# ESP32_Clock_Easy.net
KiCad netlist of a schematic drawn in EasyEDA
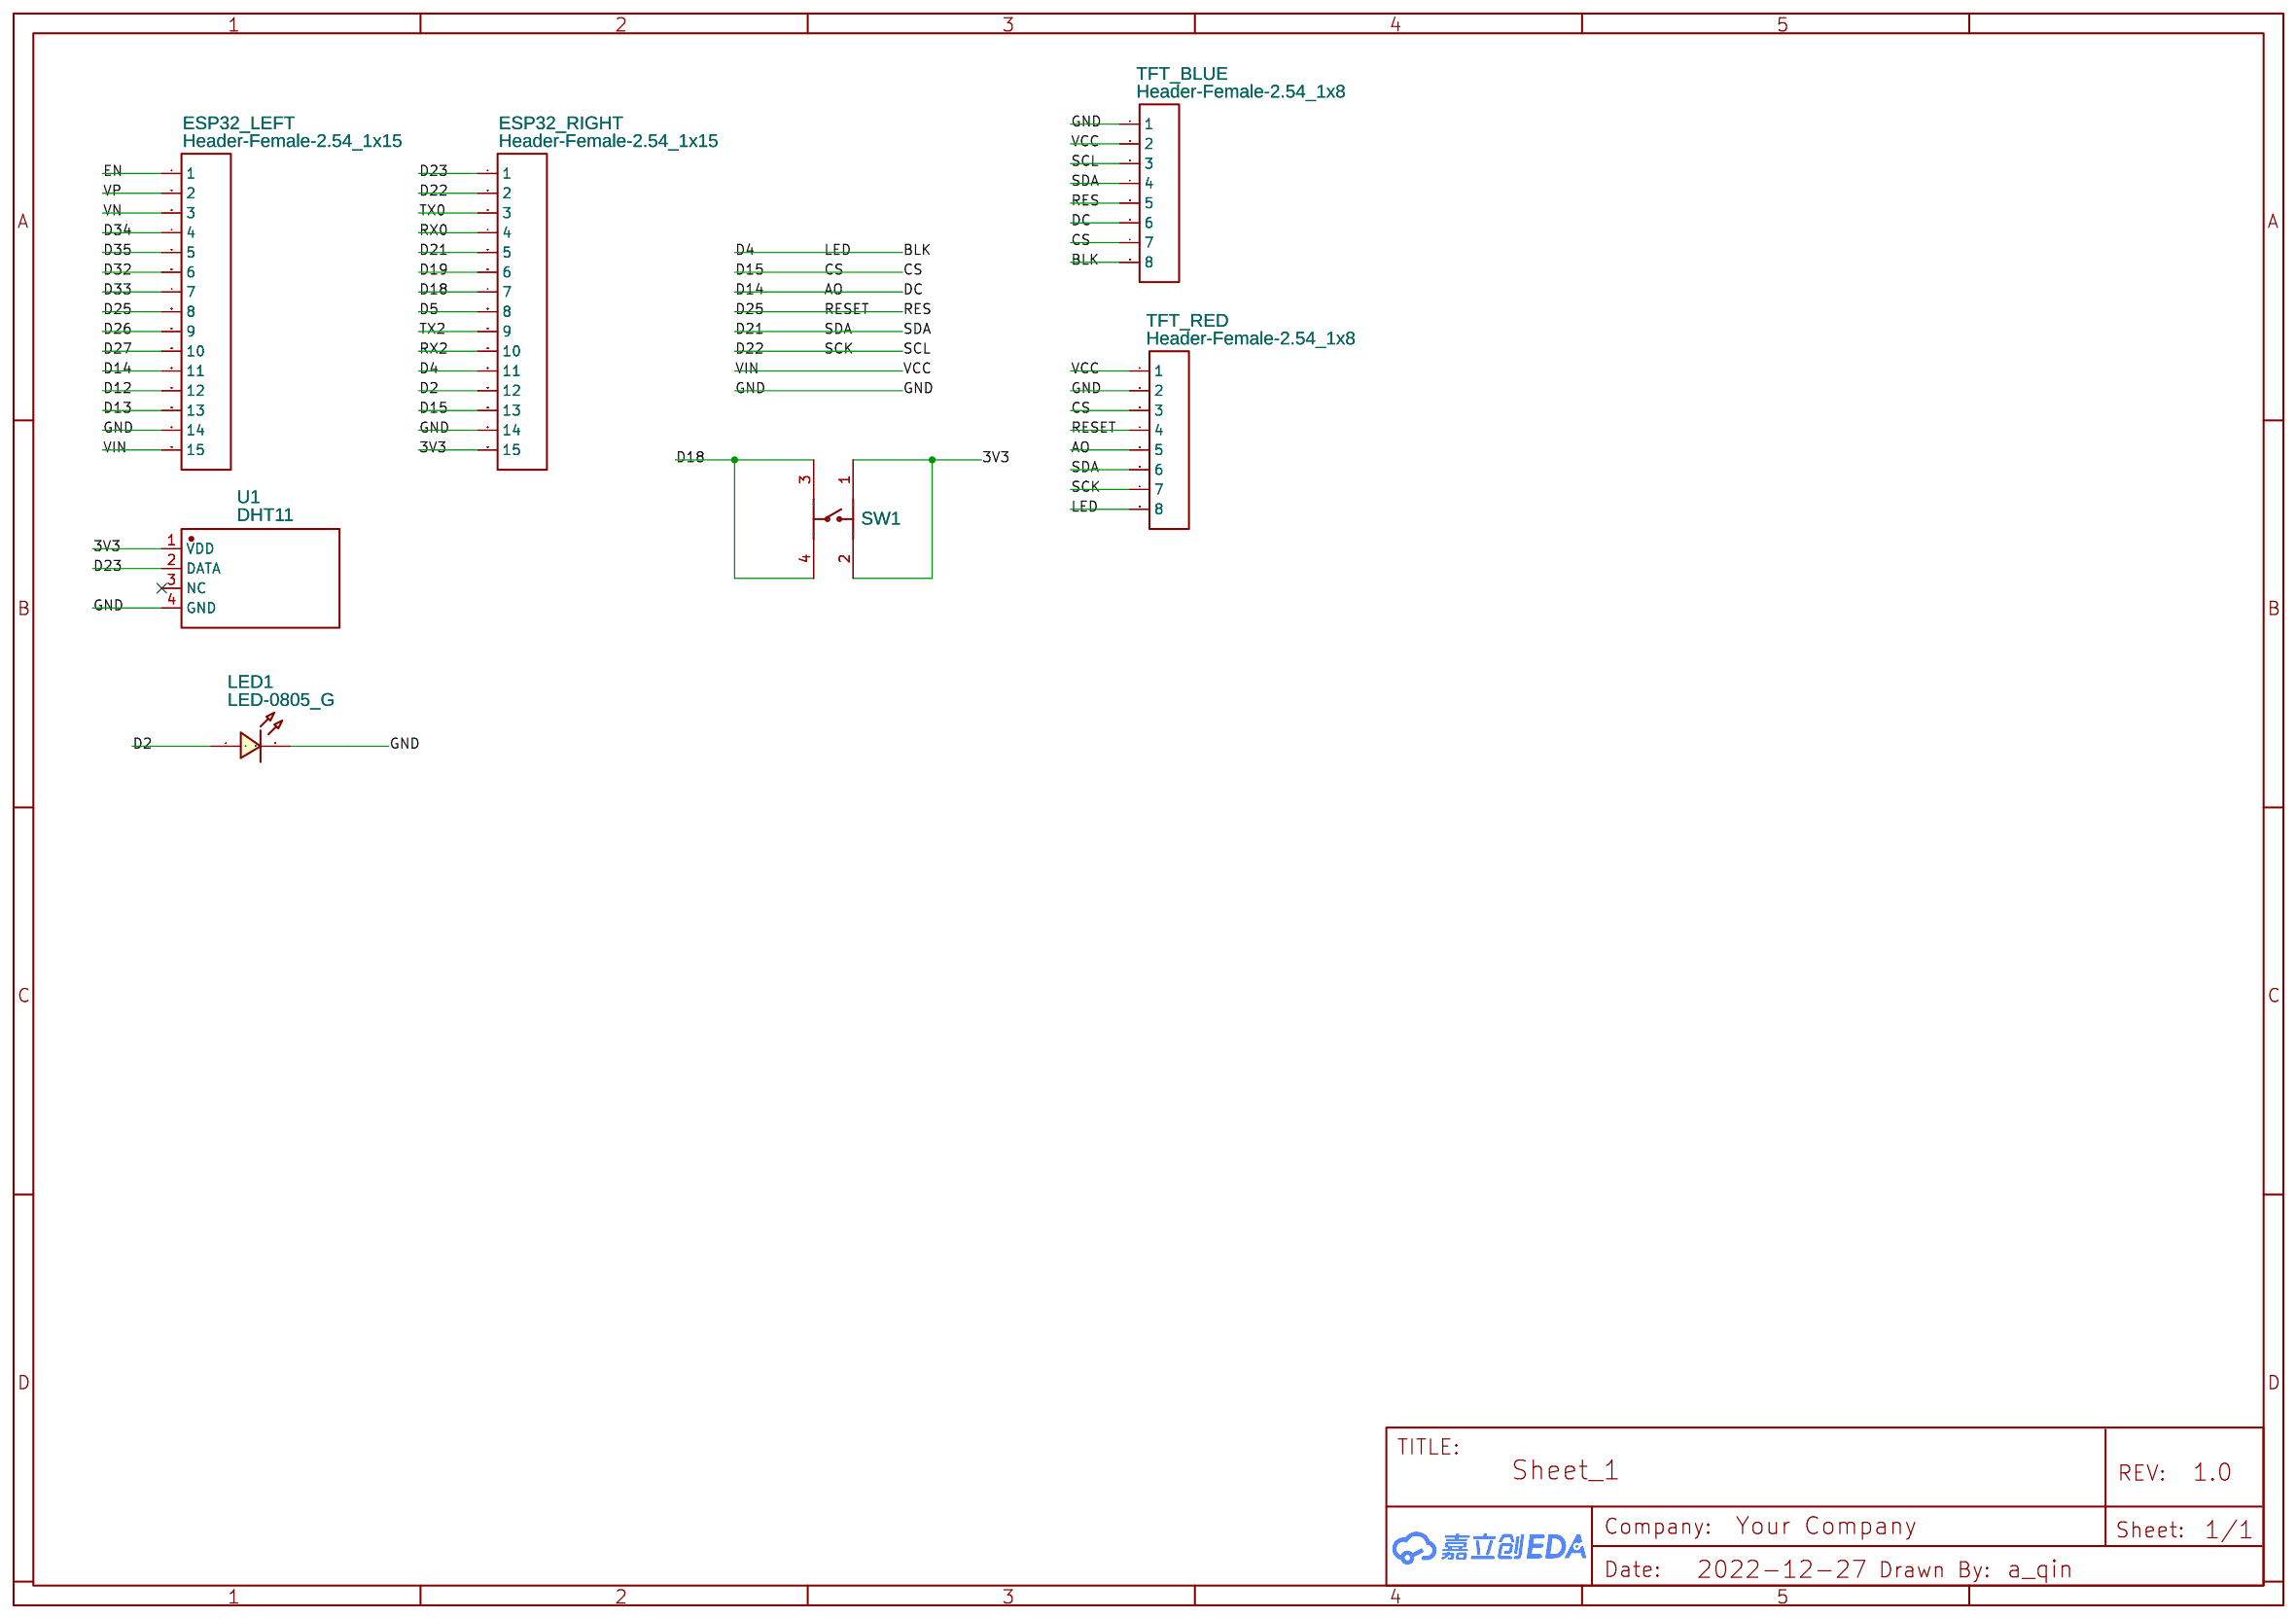
[diagram p0: schematic sheet]

(export (version "E")
  (design (tool "Eeschema 10.0.6"))
  (components
    (comp (ref "ESP32_LEFT")
      (value "Header-Female-2.54_1x15")
      (fields
        (field (name "BOM_Manufacturer Part") "B-2200S15P-A120")
        (field (name "BOM_Supplier Part") "C124408")
      )
      (libsource (lib "") (part "Header-Female-2.54_1x15"))
    )
    (comp (ref "ESP32_RIGHT")
      (value "Header-Female-2.54_1x15")
      (fields
        (field (name "BOM_Manufacturer Part") "B-2200S15P-A120")
        (field (name "BOM_Supplier Part") "C124408")
      )
      (libsource (lib "") (part "Header-Female-2.54_1x15_1"))
    )
    (comp (ref "LED1")
      (value "LED-0805_G")
      (fields (field (name "BOM_Manufacturer Part") "NCD0805G1") (field (name "BOM_Supplier Part") "C84260"))
      (libsource (lib "") (part "LED-0805_G"))
    )
    (comp (ref "SW1")
      (value "PTS645SK50-2LFS")
      (fields (field (name "BOM_Supplier Part") "C2689653"))
      (libsource (lib "") (part "PTS645SK50-2LFS"))
    )
    (comp (ref "TFT_BLUE")
      (value "Header-Female-2.54_1x8")
      (fields
        (field (name "BOM_Manufacturer Part") "2.54-1*8P母环保")
        (field (name "BOM_Supplier Part") "C27438")
      )
      (libsource (lib "") (part "Header-Female-2.54_1x8"))
    )
    (comp (ref "TFT_RED")
      (value "Header-Female-2.54_1x8")
      (fields
        (field (name "BOM_Manufacturer Part") "2.54-1*8P母环保")
        (field (name "BOM_Supplier Part") "C27438")
      )
      (libsource (lib "") (part "Header-Female-2.54_1x8_1"))
    )
    (comp (ref "U1")
      (value "DHT11")
      (fields (field (name "BOM_Supplier Part") "C117051"))
      (libsource (lib "") (part "DHT11"))
    )
  )
  (nets
    (net (code "1") (name "/3V3") (class "Default")
      (node (ref "ESP32_RIGHT") (pin "15") (pinfunction "15_15") (pintype "unspecified"))
      (node (ref "SW1") (pin "1") (pinfunction "1_1") (pintype "unspecified"))
      (node (ref "SW1") (pin "2") (pinfunction "2_2") (pintype "unspecified"))
      (node (ref "U1") (pin "1") (pinfunction "VDD_1") (pintype "unspecified"))
    )
    (net (code "2") (name "/AO") (class "Default")
      (node (ref "ESP32_LEFT") (pin "11") (pinfunction "11_11") (pintype "unspecified"))
      (node (ref "TFT_BLUE") (pin "6") (pinfunction "6_6") (pintype "input"))
      (node (ref "TFT_RED") (pin "5") (pinfunction "5_5") (pintype "input"))
    )
    (net (code "3") (name "/BLK") (class "Default")
      (node (ref "ESP32_RIGHT") (pin "11") (pinfunction "11_11") (pintype "unspecified"))
      (node (ref "TFT_BLUE") (pin "8") (pinfunction "8_8") (pintype "input"))
      (node (ref "TFT_RED") (pin "8") (pinfunction "8_8") (pintype "input"))
    )
    (net (code "4") (name "/CS") (class "Default")
      (node (ref "ESP32_RIGHT") (pin "13") (pinfunction "13_13") (pintype "unspecified"))
      (node (ref "TFT_BLUE") (pin "7") (pinfunction "7_7") (pintype "input"))
      (node (ref "TFT_RED") (pin "3") (pinfunction "3_3") (pintype "input"))
    )
    (net (code "5") (name "/D2") (class "Default")
      (node (ref "ESP32_RIGHT") (pin "12") (pinfunction "12_12") (pintype "unspecified"))
      (node (ref "LED1") (pin "1") (pinfunction "1_1") (pintype "unspecified"))
    )
    (net (code "6") (name "/D5") (class "Default")
      (node (ref "ESP32_RIGHT") (pin "8") (pinfunction "8_8") (pintype "unspecified"))
    )
    (net (code "7") (name "/D12") (class "Default")
      (node (ref "ESP32_LEFT") (pin "12") (pinfunction "12_12") (pintype "unspecified"))
    )
    (net (code "8") (name "/D13") (class "Default")
      (node (ref "ESP32_LEFT") (pin "13") (pinfunction "13_13") (pintype "unspecified"))
    )
    (net (code "9") (name "/D18") (class "Default")
      (node (ref "ESP32_RIGHT") (pin "7") (pinfunction "7_7") (pintype "unspecified"))
      (node (ref "SW1") (pin "3") (pinfunction "3_3") (pintype "unspecified"))
      (node (ref "SW1") (pin "4") (pinfunction "4_4") (pintype "unspecified"))
    )
    (net (code "10") (name "/D19") (class "Default")
      (node (ref "ESP32_RIGHT") (pin "6") (pinfunction "6_6") (pintype "unspecified"))
    )
    (net (code "11") (name "/D21") (class "Default")
      (node (ref "ESP32_RIGHT") (pin "5") (pinfunction "5_5") (pintype "unspecified"))
      (node (ref "TFT_BLUE") (pin "4") (pinfunction "4_4") (pintype "input"))
      (node (ref "TFT_RED") (pin "6") (pinfunction "6_6") (pintype "input"))
    )
    (net (code "12") (name "/D22") (class "Default")
      (node (ref "ESP32_RIGHT") (pin "2") (pinfunction "2_2") (pintype "unspecified"))
      (node (ref "TFT_BLUE") (pin "3") (pinfunction "3_3") (pintype "input"))
      (node (ref "TFT_RED") (pin "7") (pinfunction "7_7") (pintype "input"))
    )
    (net (code "13") (name "/D23") (class "Default")
      (node (ref "ESP32_RIGHT") (pin "1") (pinfunction "1_1") (pintype "unspecified"))
      (node (ref "U1") (pin "2") (pinfunction "DATA_2") (pintype "unspecified"))
    )
    (net (code "14") (name "/D25") (class "Default")
      (node (ref "ESP32_LEFT") (pin "8") (pinfunction "8_8") (pintype "unspecified"))
      (node (ref "TFT_BLUE") (pin "5") (pinfunction "5_5") (pintype "input"))
      (node (ref "TFT_RED") (pin "4") (pinfunction "4_4") (pintype "input"))
    )
    (net (code "15") (name "/D26") (class "Default")
      (node (ref "ESP32_LEFT") (pin "9") (pinfunction "9_9") (pintype "unspecified"))
    )
    (net (code "16") (name "/D27") (class "Default")
      (node (ref "ESP32_LEFT") (pin "10") (pinfunction "10_10") (pintype "unspecified"))
    )
    (net (code "17") (name "/D32") (class "Default")
      (node (ref "ESP32_LEFT") (pin "6") (pinfunction "6_6") (pintype "unspecified"))
    )
    (net (code "18") (name "/D33") (class "Default")
      (node (ref "ESP32_LEFT") (pin "7") (pinfunction "7_7") (pintype "unspecified"))
    )
    (net (code "19") (name "/D34") (class "Default")
      (node (ref "ESP32_LEFT") (pin "4") (pinfunction "4_4") (pintype "unspecified"))
    )
    (net (code "20") (name "/D35") (class "Default")
      (node (ref "ESP32_LEFT") (pin "5") (pinfunction "5_5") (pintype "unspecified"))
    )
    (net (code "21") (name "/EN") (class "Default")
      (node (ref "ESP32_LEFT") (pin "1") (pinfunction "1_1") (pintype "unspecified"))
    )
    (net (code "22") (name "/GND") (class "Default")
      (node (ref "ESP32_LEFT") (pin "14") (pinfunction "14_14") (pintype "unspecified"))
      (node (ref "ESP32_RIGHT") (pin "14") (pinfunction "14_14") (pintype "unspecified"))
      (node (ref "LED1") (pin "2") (pinfunction "2_2") (pintype "unspecified"))
      (node (ref "TFT_BLUE") (pin "1") (pinfunction "1_1") (pintype "input"))
      (node (ref "TFT_RED") (pin "2") (pinfunction "2_2") (pintype "input"))
      (node (ref "U1") (pin "4") (pinfunction "GND_4") (pintype "unspecified"))
    )
    (net (code "23") (name "/RX0") (class "Default")
      (node (ref "ESP32_RIGHT") (pin "4") (pinfunction "4_4") (pintype "unspecified"))
    )
    (net (code "24") (name "/RX2") (class "Default")
      (node (ref "ESP32_RIGHT") (pin "10") (pinfunction "10_10") (pintype "unspecified"))
    )
    (net (code "25") (name "/TX0") (class "Default")
      (node (ref "ESP32_RIGHT") (pin "3") (pinfunction "3_3") (pintype "unspecified"))
    )
    (net (code "26") (name "/TX2") (class "Default")
      (node (ref "ESP32_RIGHT") (pin "9") (pinfunction "9_9") (pintype "unspecified"))
    )
    (net (code "27") (name "/VCC") (class "Default")
      (node (ref "ESP32_LEFT") (pin "15") (pinfunction "15_15") (pintype "unspecified"))
      (node (ref "TFT_BLUE") (pin "2") (pinfunction "2_2") (pintype "input"))
      (node (ref "TFT_RED") (pin "1") (pinfunction "1_1") (pintype "input"))
    )
    (net (code "28") (name "/VN") (class "Default")
      (node (ref "ESP32_LEFT") (pin "3") (pinfunction "3_3") (pintype "unspecified"))
    )
    (net (code "29") (name "/VP") (class "Default")
      (node (ref "ESP32_LEFT") (pin "2") (pinfunction "2_2") (pintype "unspecified"))
    )
    (net (code "30") (name "unconnected-(U1-NC-Pad3)") (class "Default")
      (node (ref "U1") (pin "3") (pinfunction "NC_3") (pintype "unspecified+no_connect"))
    )
  )
)
